# Gate_Driver_Board.net
KiCad netlist of a schematic drawn in Altium Designer
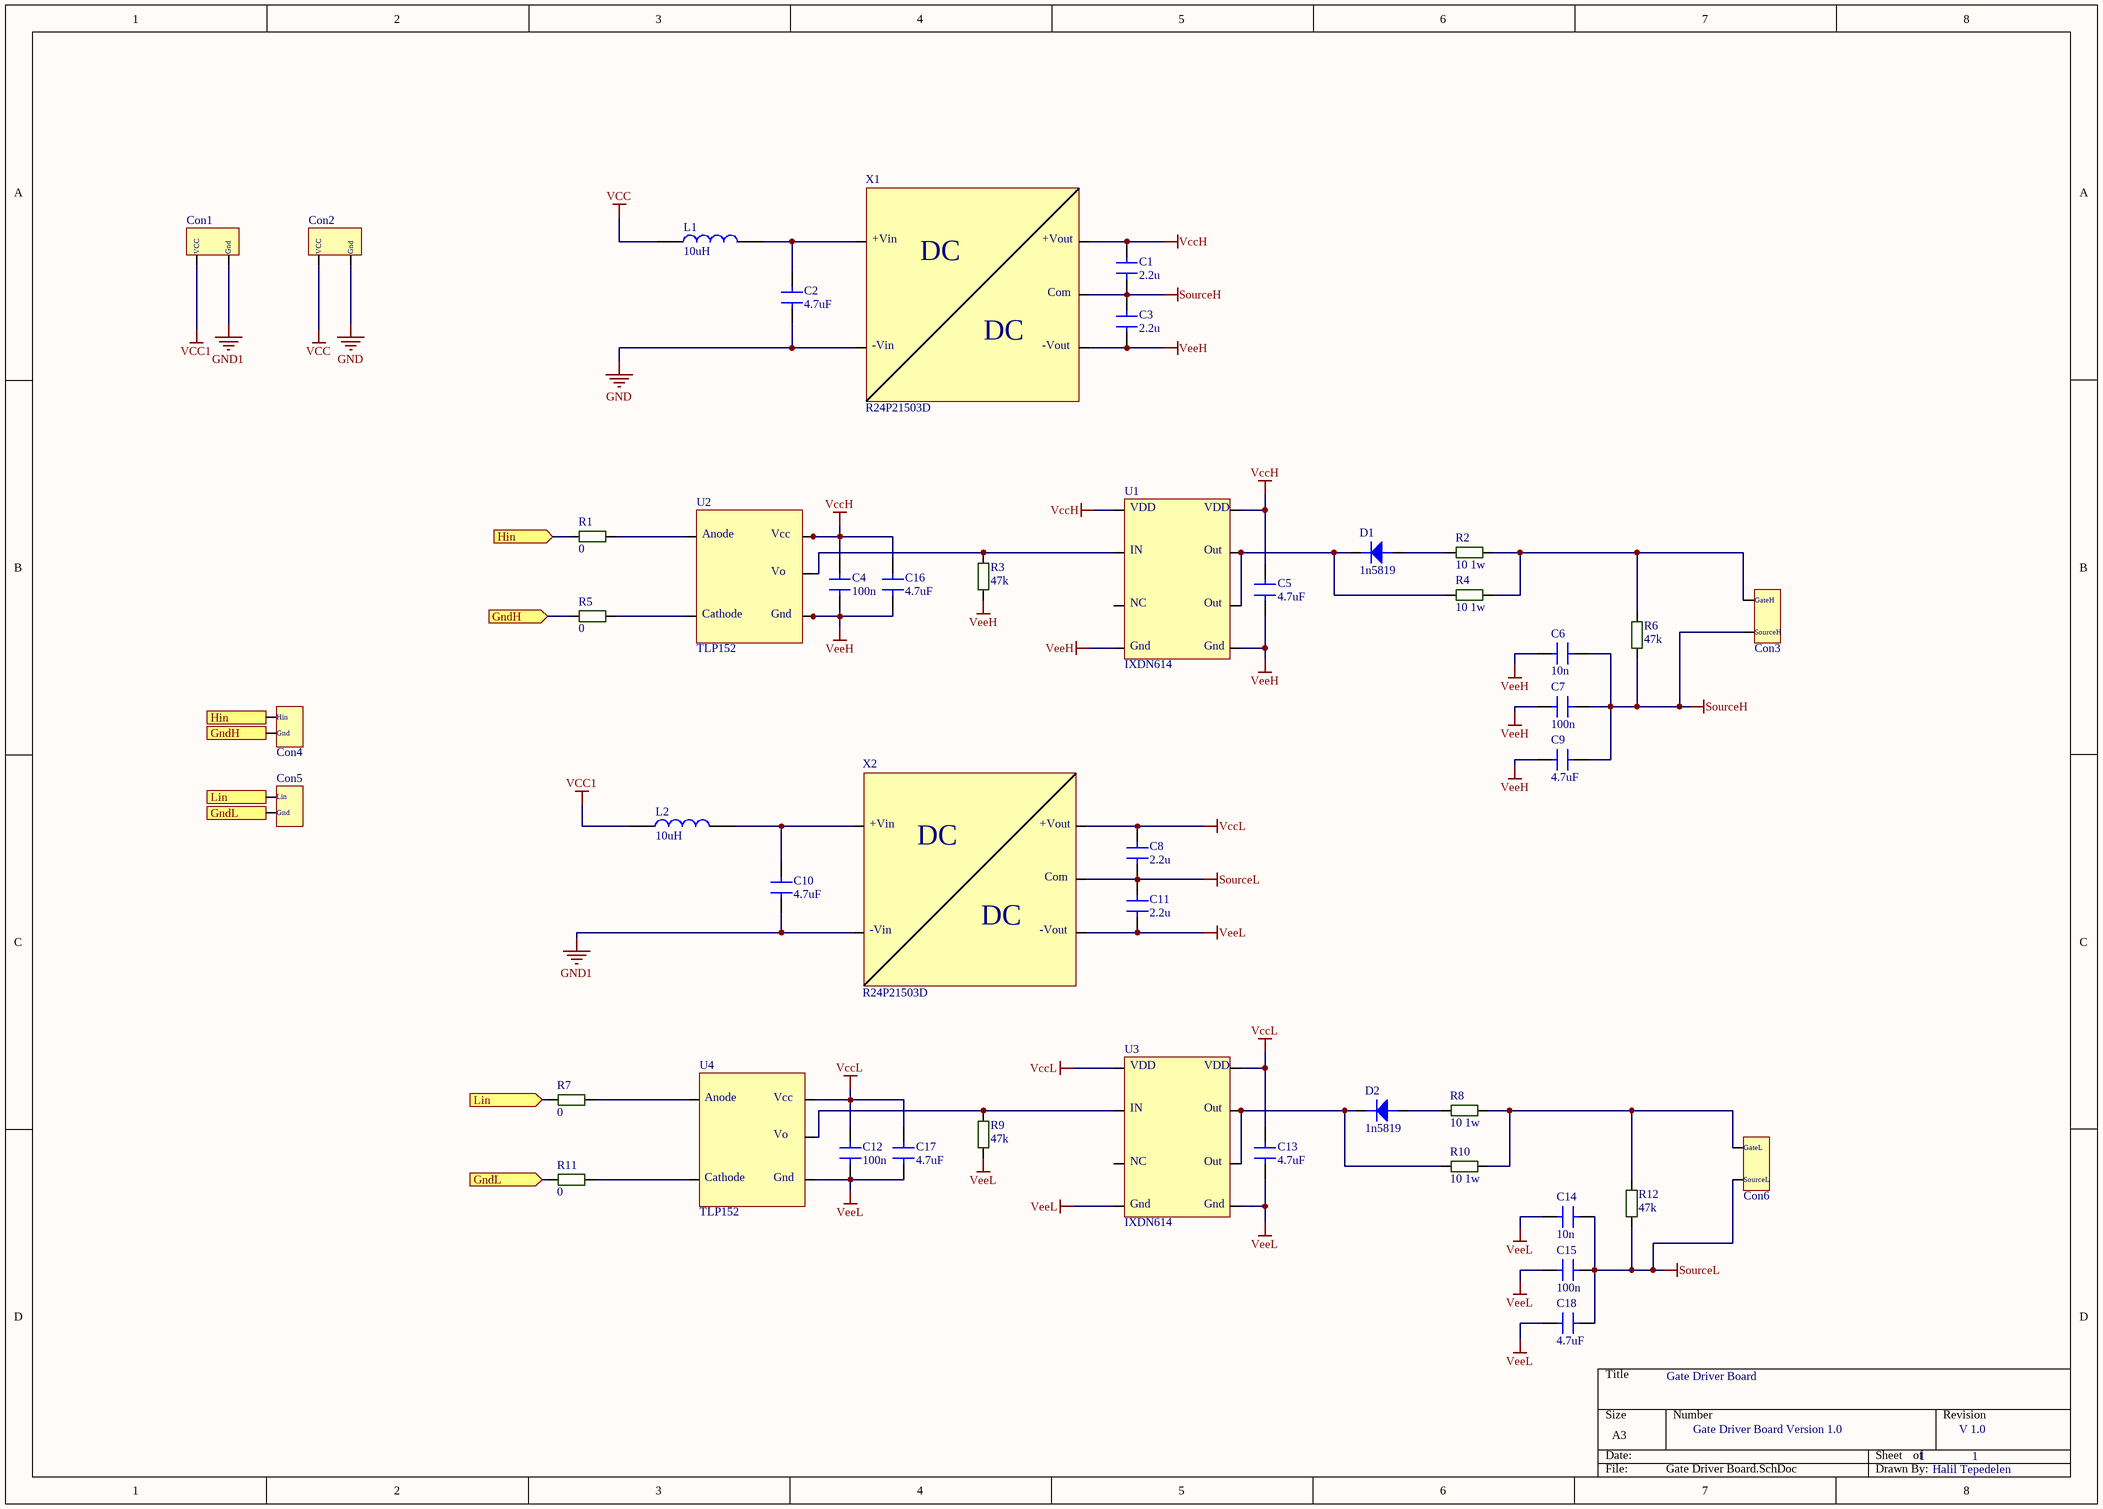
[diagram p0: Gate Driver Board.SchDoc]

(export (version "E")
  (design (tool "Eeschema 10.0.6"))
  (components
    (comp (ref "C1")
      (value "2.2u")
      (footprint "C-0805")
      (description "MLCC (2012) 0805 2.2uF 50VDC ±10% X5R")
      (fields (field (name "MANUFACTURER") "SAMSUNG") (field (name "ÖZDISAN PART NUMBER") " CL21A225KBQNNNE"))
      (libsource (lib "Gate Driver Board") (part "C-0805"))
    )
    (comp (ref "C2")
      (value "4.7uF")
      (footprint "Gate Driver Board:C-1206")
      (description "MLCC (3216) 1206 4.7uF 50VDC ±10% X7R")
      (fields (field (name "ÖZDISAN PART NUMBER") "CL31B475KBHNNNE") (field (name "MANUFACTURER") "SAMSUNG"))
      (libsource (lib "Gate Driver Board") (part "Cap1206"))
    )
    (comp (ref "C3")
      (value "2.2u")
      (footprint "C-0805")
      (description "MLCC (2012) 0805 2.2uF 50VDC ±10% X5R")
      (fields (field (name "MANUFACTURER") "SAMSUNG") (field (name "ÖZDISAN PART NUMBER") "CL21A225KBQNNNE"))
      (libsource (lib "Gate Driver Board") (part "C-0805"))
    )
    (comp (ref "C4")
      (value "100n")
      (footprint "C-0805")
      (description "MLCC (2012) 0805 100nF 50VDC ±10% X7RMLCC (2012) 0805 100nF 50VDC ±10% X7R")
      (fields (field (name "MANUFACTURER") "SAMSUNG") (field (name "ÖZDISAN PART NUMBER") "CL21B104KBCNNNC"))
      (libsource (lib "Gate Driver Board") (part "C-0805"))
    )
    (comp (ref "C5")
      (value "4.7uF")
      (footprint "Gate Driver Board:C-1206")
      (description "MLCC (3216) 1206 4.7uF 50VDC ±10% X7R")
      (fields (field (name "ÖZDISAN PART NUMBER") "CL31B475KBHNNNE") (field (name "MANUFACTURER") "SAMSUNG"))
      (libsource (lib "Gate Driver Board") (part "C-1206"))
    )
    (comp (ref "C6")
      (value "10n")
      (footprint "C-0805")
      (description "MLCC (2012) 0805 10nF 50VDC ±10% X7R")
      (fields (field (name "MANUFACTURER") "SAMSUNG") (field (name "ÖZDISAN PART NUMBER") "CL21B103KBANNNL"))
      (libsource (lib "Gate Driver Board") (part "C-0805"))
    )
    (comp (ref "C7")
      (value "100n")
      (footprint "C-0805")
      (description "MLCC (2012) 0805 100nF 50VDC ±10% X7R")
      (fields (field (name "ÖZDISAN PART NUMBER") "CL21B104KBCNNNC") (field (name "MANUFACTURER") "SAMSUNG"))
      (libsource (lib "Gate Driver Board") (part "C-0805"))
    )
    (comp (ref "C8")
      (value "2.2u")
      (footprint "C-0805")
      (description "MLCC (2012) 0805 2.2uF 50VDC ±10% X5R")
      (fields (field (name "MANUFACTURER") "SAMSUNG") (field (name "ÖZDISAN PART NUMBER") "CL21A225KBQNNNE"))
      (libsource (lib "Gate Driver Board") (part "C-0805"))
    )
    (comp (ref "C9")
      (value "4.7uF")
      (footprint "Gate Driver Board:C-1206")
      (description "MLCC (3216) 1206 4.7uF 50VDC ±10% X7R")
      (fields (field (name "ÖZDISAN PART NUMBER") " CL31B475KBHNNNE") (field (name "MANUFACTURER") "SAMSUNG"))
      (libsource (lib "Gate Driver Board") (part "Cap1206"))
    )
    (comp (ref "C10")
      (value "4.7uF")
      (footprint "Gate Driver Board:C-1206")
      (description "MLCC (3216) 1206 4.7uF 50VDC ±10% X7R")
      (fields (field (name "ÖZDISAN PART NUMBER") " CL31B475KBHNNNE") (field (name "MANUFACTURER") "SAMSUNG"))
      (libsource (lib "Gate Driver Board") (part "Cap1206"))
    )
    (comp (ref "C11")
      (value "2.2u")
      (footprint "C-0805")
      (description "MLCC (2012) 0805 2.2uF 50VDC ±10% X5R")
      (fields (field (name "MANUFACTURER") "SAMSUNG") (field (name "ÖZDISAN PART NUMBER") "CL21A225KBQNNNE"))
      (libsource (lib "Gate Driver Board") (part "C-0805"))
    )
    (comp (ref "C12")
      (value "100n")
      (footprint "C-0805")
      (description "MLCC (2012) 0805 100nF 50VDC ±10% X7R")
      (fields (field (name "ÖZDISAN PART NUMBER") "CL21B104KBCNNNC") (field (name "MANUFACTURER") "SAMSUNG"))
      (libsource (lib "Gate Driver Board") (part "C-0805"))
    )
    (comp (ref "C13")
      (value "4.7uF")
      (footprint "Gate Driver Board:C-1206")
      (description "MLCC (3216) 1206 4.7uF 50VDC ±10% X7R")
      (fields (field (name "ÖZDISAN PART NUMBER") "CL31B475KBHNNNE") (field (name "MANUFACTURER") "SAMSUNG"))
      (libsource (lib "Gate Driver Board") (part "C-1206"))
    )
    (comp (ref "C14")
      (value "10n")
      (footprint "C-0805")
      (description "MLCC (2012) 0805 10nF 50VDC ±10% X7R")
      (fields (field (name "ÖZDISAN PART NUMBER") "CL21B103KBANNNL") (field (name "MANUFACTURER") "SAMSUNG"))
      (libsource (lib "Gate Driver Board") (part "C-0805"))
    )
    (comp (ref "C15")
      (value "100n")
      (footprint "C-0805")
      (description "MLCC (2012) 0805 100nF 50VDC ±10% X7R")
      (fields (field (name "ÖZDISAN PART NUMBER") "CL21B104KBCNNNC") (field (name "MANUFACTURER") "SAMSUNG"))
      (libsource (lib "Gate Driver Board") (part "C-0805"))
    )
    (comp (ref "C16")
      (value "4.7uF")
      (footprint "Gate Driver Board:C-1206")
      (description "MLCC (3216) 1206 4.7uF 50VDC ±10% X7R")
      (fields (field (name "ÖZDISAN PART NUMBER") "CL31B475KBHNNNE") (field (name "MANUFACTURER") "SAMSUNG"))
      (libsource (lib "Gate Driver Board") (part "C-1206"))
    )
    (comp (ref "C17")
      (value "4.7uF")
      (footprint "Gate Driver Board:C-1206")
      (description "MLCC (3216) 1206 4.7uF 50VDC ±10% X7R")
      (fields (field (name "ÖZDISAN PART NUMBER") "CL31B475KBHNNNE") (field (name "MANUFACTURER") "SAMSUNG"))
      (libsource (lib "Gate Driver Board") (part "C-1206"))
    )
    (comp (ref "C18")
      (value "4.7uF")
      (footprint "Gate Driver Board:C-1206")
      (description "MLCC (3216) 1206 4.7uF 50VDC ±10% X7R")
      (fields (field (name "ÖZDISAN PART NUMBER") "CL31B475KBHNNNE") (field (name "MANUFACTURER") "SAMSUNG"))
      (libsource (lib "Gate Driver Board") (part "Cap1206"))
    )
    (comp (ref "Con1")
      (value "Connector")
      (footprint "Conn")
      (description "PIN HEADER 40PIN(1x40) 2.54mm THT V/T")
      (fields
        (field (name "ÖZDISAN PART NUMBER") "KLS1-207-1-40-S-3X9.5X15")
        (field (name "MANUFACTURER") "KLS ELECTRONIC")
      )
      (libsource (lib "Gate Driver Board") (part "Connector"))
    )
    (comp (ref "Con2")
      (value "Connector")
      (footprint "Conn")
      (description "PIN HEADER 40PIN(1x40) 2.54mm THT V/T")
      (fields
        (field (name "ÖZDISAN PART NUMBER") "KLS1-207-1-40-S-3X9.5X15")
        (field (name "MANUFACTURER") "KLS ELECTRONIC")
      )
      (libsource (lib "Gate Driver Board") (part "Connector"))
    )
    (comp (ref "Con3")
      (value "Connector2_1")
      (footprint "Conn")
      (description "PIN HEADER 40PIN(1x40) 2.54mm THT V/T")
      (fields
        (field (name "ÖZDISAN PART NUMBER") " KLS1-207-1-40-S-3X9.5X15")
        (field (name "MANUFACTURER") "KLS ELECTRONIC")
      )
      (libsource (lib "Gate Driver Board") (part "Connector2_1"))
    )
    (comp (ref "Con4")
      (value "Connector2")
      (footprint "Conn")
      (description "PIN HEADER 40PIN(1x40) 2.54mm THT V/T")
      (fields
        (field (name "ÖZDISAN PART NUMBER") "KLS1-207-1-40-S-3X9.5X15")
        (field (name "MANUFACTURER") "KLS ELECTRONIC")
      )
      (libsource (lib "Gate Driver Board") (part "Connector2"))
    )
    (comp (ref "Con5")
      (value "Connector3")
      (footprint "Conn")
      (description "PIN HEADER 40PIN(1x40) 2.54mm THT V/T")
      (fields
        (field (name "ÖZDISAN PART NUMBER") "KLS1-207-1-40-S-3X9.5X15")
        (field (name "MANUFACTURER") "KLS ELECTRONIC")
      )
      (libsource (lib "Gate Driver Board") (part "Connector3"))
    )
    (comp (ref "Con6")
      (value "Connector2_2")
      (footprint "Conn")
      (description "PIN HEADER 40PIN(1x40) 2.54mm THT V/T")
      (fields
        (field (name "ÖZDISAN PART NUMBER") "KLS1-207-1-40-S-3X9.5X15")
        (field (name "MANUFACTURER") "KLS ELECTRONIC")
      )
      (libsource (lib "Gate Driver Board") (part "Connector2_2"))
    )
    (comp (ref "D1")
      (value "1n5819")
      (footprint "LFI Power Board PcbLib1:SOD123")
      (description "DIODE SCHOTTKY 1A 40V SOD123")
      (fields (field (name "MANUFACTURER") "HOTTECH") (field (name "ÖZDISAN PART NUMBER") "B5819W"))
      (libsource (lib "Gate Driver Board") (part "1N4148W-E3-18"))
    )
    (comp (ref "D2")
      (value "1n5819")
      (footprint "LFI Power Board PcbLib1:SOD123")
      (description "Diode Small Signal Switching 100V 0.15A 2-Pin SOD-123 T/R")
      (fields (field (name "ÖZDISAN PART NUMBER") "B5819W") (field (name "MANUFACTURER") "HOTTECH"))
      (libsource (lib "Gate Driver Board") (part "1N4148W-E3-18"))
    )
    (comp (ref "L1")
      (value "10uH")
      (footprint "Gate Driver Board:WE-TPC_282892")
      (description "INDUCTOR POWER 10UH 2.8X2.8X2.8MM SMD")
      (fields (field (name "ÖZDISAN PART NUMBER") "744025100") (field (name "MANUFACTURER") "WURTH"))
      (libsource (lib "Gate Driver Board") (part "inductor"))
    )
    (comp (ref "L2")
      (value "10uH")
      (footprint "WE-TPC_282892")
      (description "INDUCTOR POWER 10UH 2.8X2.8X2.8MM SMD")
      (fields (field (name "ÖZDISAN PART NUMBER") "744025100") (field (name "MANUFACTURER") "WURTH"))
      (libsource (lib "Gate Driver Board") (part "inductor"))
    )
    (comp (ref "R1")
      (value "0")
      (footprint "Gate Driver Board:R-0805")
      (description "RES.(2012) 0805 0 Ohms 5% 1/8W-S 800PPM")
      (fields (field (name "MANUFACTURER") "ROYALOHM") (field (name "ÖZDISAN PART NUMBER") "0805S8J0000T5E"))
      (libsource (lib "Gate Driver Board") (part "Res0805"))
    )
    (comp (ref "R2")
      (value "10 1w")
      (footprint "R-2512")
      (description "RES.(6432) 2512 5.1 Ohms 5% 1W 400PPM")
      (fields (field (name "MANUFACTURER") "ROYALOHM") (field (name "ÖZDISAN PART NUMBER") "25121WJ051JT4E"))
      (libsource (lib "Gate Driver Board") (part "R-2512"))
    )
    (comp (ref "R3")
      (value "47k")
      (footprint "Gate Driver Board:R-0805")
      (description "RES.(2012) 0805 47K Ohms 5% 1/8W-S 100PPM")
      (fields (field (name "MANUFACTURER") "ROYALOHM") (field (name "ÖZDISAN PART NUMBER") "0805S8J0473T5E"))
      (libsource (lib "Gate Driver Board") (part "Res0805"))
    )
    (comp (ref "R4")
      (value "10 1w")
      (footprint "R-2512")
      (description "RES.(6432) 2512 5.1 Ohms 5% 1W 400PPM")
      (fields (field (name "ÖZDISAN PART NUMBER") "25121WJ051JT4E") (field (name "MANUFACTURER") "ROYALOHM"))
      (libsource (lib "Gate Driver Board") (part "R-2512"))
    )
    (comp (ref "R5")
      (value "0")
      (footprint "Gate Driver Board:R-0805")
      (description "RES.(2012) 0805 0 Ohms 5% 1/8W-S 800PPM")
      (fields (field (name "MANUFACTURER") "ROYALOHM") (field (name "ÖZDISAN PART NUMBER") "0805S8J0000T5E"))
      (libsource (lib "Gate Driver Board") (part "Res0805"))
    )
    (comp (ref "R6")
      (value "47k")
      (footprint "Gate Driver Board:R-0805")
      (description "RES.(2012) 0805 47K Ohms 5% 1/8W-S 100PPM")
      (fields (field (name "ÖZDISAN PART NUMBER") "0805S8J0473T5E") (field (name "MANUFACTURER") "ROYALOHM"))
      (libsource (lib "Gate Driver Board") (part "Res0805"))
    )
    (comp (ref "R7")
      (value "0")
      (footprint "Gate Driver Board:R-0805")
      (description "RES.(2012) 0805 0 Ohms 5% 1/8W-S 800PPM")
      (fields (field (name "ÖZDISAN PART NUMBER") "0805S8J0000T5E") (field (name "MANUFACTURER") "ROYALOHM"))
      (libsource (lib "Gate Driver Board") (part "Res0805"))
    )
    (comp (ref "R8")
      (value "10 1w")
      (footprint "R-2512")
      (description "RES.(6432) 2512 5.1 Ohms 5% 1W 400PPM")
      (fields (field (name "ÖZDISAN PART NUMBER") "25121WJ051JT4E") (field (name "MANUFACTURER") "ROYALOHM"))
      (libsource (lib "Gate Driver Board") (part "R-2512"))
    )
    (comp (ref "R9")
      (value "47k")
      (footprint "Gate Driver Board:R-0805")
      (description "RES.(2012) 0805 47K Ohms 5% 1/8W-S 100PPM")
      (fields (field (name "ÖZDISAN PART NUMBER") "0805S8J0473T5E") (field (name "MANUFACTURER") "ROYALOHM"))
      (libsource (lib "Gate Driver Board") (part "Res0805"))
    )
    (comp (ref "R10")
      (value "10 1w")
      (footprint "R-2512")
      (description "RES.(6432) 2512 5.1 Ohms 5% 1W 400PPM")
      (fields (field (name "MANUFACTURER") "ROYALOHM") (field (name "ÖZDISAN PART NUMBER") "25121WJ051JT4E"))
      (libsource (lib "Gate Driver Board") (part "R-2512"))
    )
    (comp (ref "R11")
      (value "0")
      (footprint "Gate Driver Board:R-0805")
      (description "RES.(2012) 0805 0 Ohms 5% 1/8W-S 800PPM")
      (fields (field (name "MANUFACTURER") "ROYALOHM") (field (name "ÖZDISAN PART NUMBER") "0805S8J0000T5E"))
      (libsource (lib "Gate Driver Board") (part "Res0805"))
    )
    (comp (ref "R12")
      (value "47k")
      (footprint "Gate Driver Board:R-0805")
      (description "RES.(2012) 0805 47K Ohms 5% 1/8W-S 100PPM")
      (fields (field (name "ÖZDISAN PART NUMBER") "0805S8J0473T5E") (field (name "MANUFACTURER") "ROYALOHM"))
      (libsource (lib "Gate Driver Board") (part "Res0805"))
    )
    (comp (ref "U1")
      (value "IXDN614")
      (footprint "FAN3122 Soic8")
      (description "IC-614 DRIVER MOSFET/IGBT SOIC8 IXYS CLARE")
      (fields (field (name "MANUFACTURER") "IXYS CLARE") (field (name "ÖZDISAN PART NUMBER") "IXDN614SI"))
      (libsource (lib "Gate Driver Board") (part "IXDN614SITR"))
    )
    (comp (ref "U2")
      (value "TLP152")
      (footprint "TLP152")
      (description "IC-152 PHOTOCOUPLER GATE DRIVE SO6 TOSHIBA")
      (fields (field (name "ÖZDISAN PART NUMBER") "TLP152(TPL,E") (field (name "MANUFACTURER") "TOSHIBA"))
      (libsource (lib "Gate Driver Board") (part "TLP152(TPL,E"))
    )
    (comp (ref "U3")
      (value "IXDN614")
      (footprint "FAN3122 Soic8")
      (description "IC-614 DRIVER MOSFET/IGBT SOIC8 IXYS CLARE")
      (fields (field (name "MANUFACTURER") "IXYS CLARE") (field (name "ÖZDISAN PART NUMBER") "IXDN614SI"))
      (libsource (lib "Gate Driver Board") (part "IXDN614SITR"))
    )
    (comp (ref "U4")
      (value "TLP152")
      (footprint "TLP152")
      (description "IC-152 PHOTOCOUPLER GATE DRIVE SO6 TOSHIBA")
      (fields (field (name "ÖZDISAN PART NUMBER") "TLP152(TPL,E") (field (name "MANUFACTURER") "TOSHIBA"))
      (libsource (lib "Gate Driver Board") (part "TLP152(TPL,E"))
    )
    (comp (ref "X1")
      (value "R24P21503D")
      (footprint "SIP7")
      (description "DC/DC CONV 2W 12VDC +15/-3VDC 93mA/-185mA SIP7")
      (fields (field (name "MANUFACTURER") "RECOM") (field (name "ÖZDISAN PART NUMBER") "R12P21503D"))
      (libsource (lib "Gate Driver Board") (part "R24P21503D"))
    )
    (comp (ref "X2")
      (value "R24P21503D")
      (footprint "SIP7")
      (description "DC/DC CONV 2W 12VDC +15/-3VDC 93mA/-185mA SIP7")
      (fields (field (name "MANUFACTURER") "RECOM") (field (name "ÖZDISAN PART NUMBER") "R12P21503D"))
      (libsource (lib "Gate Driver Board") (part "R24P21503D"))
    )
  )
  (nets
    (net (code "1") (name "/GndH") (class "Default")
      (node (ref "Con4") (pin "2") (pinfunction "2_2") (pintype "passive"))
      (node (ref "R5") (pin "1") (pinfunction "1_1") (pintype "passive"))
    )
    (net (code "2") (name "/GndL") (class "Default")
      (node (ref "Con5") (pin "2") (pinfunction "2_2") (pintype "passive"))
      (node (ref "R11") (pin "1") (pinfunction "1_1") (pintype "passive"))
    )
    (net (code "3") (name "/Hin") (class "Default")
      (node (ref "Con4") (pin "1") (pinfunction "1_1") (pintype "passive"))
      (node (ref "R1") (pin "1") (pinfunction "1_1") (pintype "passive"))
    )
    (net (code "4") (name "/Lin") (class "Default")
      (node (ref "Con5") (pin "1") (pinfunction "1_1") (pintype "passive"))
      (node (ref "R7") (pin "1") (pinfunction "1_1") (pintype "passive"))
    )
    (net (code "5") (name "GND") (class "Default")
      (node (ref "C2") (pin "1") (pinfunction "1_1") (pintype "passive"))
      (node (ref "Con2") (pin "2") (pinfunction "2_2") (pintype "passive"))
      (node (ref "X1") (pin "2") (pinfunction "2_2") (pintype "passive"))
    )
    (net (code "6") (name "GND1") (class "Default")
      (node (ref "C10") (pin "1") (pinfunction "1_1") (pintype "passive"))
      (node (ref "Con1") (pin "2") (pinfunction "2_2") (pintype "passive"))
      (node (ref "X2") (pin "2") (pinfunction "2_2") (pintype "passive"))
    )
    (net (code "7") (name "Net-(C2-Pad2)") (class "Default")
      (node (ref "C2") (pin "2") (pinfunction "2_2") (pintype "passive"))
      (node (ref "L1") (pin "2") (pinfunction "2_2") (pintype "passive"))
      (node (ref "X1") (pin "1") (pinfunction "1_1") (pintype "passive"))
    )
    (net (code "8") (name "Net-(C10-Pad2)") (class "Default")
      (node (ref "C10") (pin "2") (pinfunction "2_2") (pintype "passive"))
      (node (ref "L2") (pin "2") (pinfunction "2_2") (pintype "passive"))
      (node (ref "X2") (pin "1") (pinfunction "1_1") (pintype "passive"))
    )
    (net (code "9") (name "Net-(Con3-Pad1)") (class "Default")
      (node (ref "Con3") (pin "1") (pinfunction "1_1") (pintype "passive"))
      (node (ref "R2") (pin "2") (pinfunction "2_2") (pintype "passive"))
      (node (ref "R4") (pin "2") (pinfunction "2_2") (pintype "passive"))
      (node (ref "R6") (pin "2") (pinfunction "2_2") (pintype "passive"))
    )
    (net (code "10") (name "Net-(Con6-Pad1)") (class "Default")
      (node (ref "Con6") (pin "1") (pinfunction "1_1") (pintype "passive"))
      (node (ref "R10") (pin "2") (pinfunction "2_2") (pintype "passive"))
      (node (ref "R12") (pin "2") (pinfunction "2_2") (pintype "passive"))
      (node (ref "R8") (pin "2") (pinfunction "2_2") (pintype "passive"))
    )
    (net (code "11") (name "Net-(D1-Pada)") (class "Default")
      (node (ref "D1") (pin "a") (pinfunction "a_a") (pintype "passive"))
      (node (ref "R2") (pin "1") (pinfunction "1_1") (pintype "passive"))
    )
    (net (code "12") (name "Net-(D1-Padk)") (class "Default")
      (node (ref "D1") (pin "k") (pinfunction "k_k") (pintype "passive"))
      (node (ref "R4") (pin "1") (pinfunction "1_1") (pintype "passive"))
      (node (ref "U1") (pin "6") (pinfunction "6_6") (pintype "passive"))
      (node (ref "U1") (pin "7") (pinfunction "7_7") (pintype "passive"))
    )
    (net (code "13") (name "Net-(D2-Pada)") (class "Default")
      (node (ref "D2") (pin "a") (pinfunction "a_a") (pintype "passive"))
      (node (ref "R8") (pin "1") (pinfunction "1_1") (pintype "passive"))
    )
    (net (code "14") (name "Net-(D2-Padk)") (class "Default")
      (node (ref "D2") (pin "k") (pinfunction "k_k") (pintype "passive"))
      (node (ref "R10") (pin "1") (pinfunction "1_1") (pintype "passive"))
      (node (ref "U3") (pin "6") (pinfunction "6_6") (pintype "passive"))
      (node (ref "U3") (pin "7") (pinfunction "7_7") (pintype "passive"))
    )
    (net (code "15") (name "Net-(R1-Pad2)") (class "Default")
      (node (ref "R1") (pin "2") (pinfunction "2_2") (pintype "passive"))
      (node (ref "U2") (pin "1") (pinfunction "1_1") (pintype "passive"))
    )
    (net (code "16") (name "Net-(R3-Pad2)") (class "Default")
      (node (ref "R3") (pin "2") (pinfunction "2_2") (pintype "passive"))
      (node (ref "U1") (pin "2") (pinfunction "2_2") (pintype "passive"))
      (node (ref "U2") (pin "4") (pinfunction "4_4") (pintype "passive"))
    )
    (net (code "17") (name "Net-(R5-Pad2)") (class "Default")
      (node (ref "R5") (pin "2") (pinfunction "2_2") (pintype "passive"))
      (node (ref "U2") (pin "2") (pinfunction "2_2") (pintype "passive"))
    )
    (net (code "18") (name "Net-(R7-Pad2)") (class "Default")
      (node (ref "R7") (pin "2") (pinfunction "2_2") (pintype "passive"))
      (node (ref "U4") (pin "1") (pinfunction "1_1") (pintype "passive"))
    )
    (net (code "19") (name "Net-(R9-Pad2)") (class "Default")
      (node (ref "R9") (pin "2") (pinfunction "2_2") (pintype "passive"))
      (node (ref "U3") (pin "2") (pinfunction "2_2") (pintype "passive"))
      (node (ref "U4") (pin "4") (pinfunction "4_4") (pintype "passive"))
    )
    (net (code "20") (name "Net-(R11-Pad2)") (class "Default")
      (node (ref "R11") (pin "2") (pinfunction "2_2") (pintype "passive"))
      (node (ref "U4") (pin "2") (pinfunction "2_2") (pintype "passive"))
    )
    (net (code "21") (name "SourceH") (class "Default")
      (node (ref "C1") (pin "1") (pinfunction "1_1") (pintype "passive"))
      (node (ref "C3") (pin "2") (pinfunction "2_2") (pintype "passive"))
      (node (ref "C6") (pin "1") (pinfunction "1_1") (pintype "passive"))
      (node (ref "C7") (pin "1") (pinfunction "1_1") (pintype "passive"))
      (node (ref "C9") (pin "2") (pinfunction "2_2") (pintype "passive"))
      (node (ref "Con3") (pin "2") (pinfunction "2_2") (pintype "passive"))
      (node (ref "R6") (pin "1") (pinfunction "1_1") (pintype "passive"))
      (node (ref "X1") (pin "6") (pinfunction "6_6") (pintype "passive"))
    )
    (net (code "22") (name "SourceL") (class "Default")
      (node (ref "C11") (pin "2") (pinfunction "2_2") (pintype "passive"))
      (node (ref "C14") (pin "1") (pinfunction "1_1") (pintype "passive"))
      (node (ref "C15") (pin "1") (pinfunction "1_1") (pintype "passive"))
      (node (ref "C18") (pin "2") (pinfunction "2_2") (pintype "passive"))
      (node (ref "C8") (pin "1") (pinfunction "1_1") (pintype "passive"))
      (node (ref "Con6") (pin "2") (pinfunction "2_2") (pintype "passive"))
      (node (ref "R12") (pin "1") (pinfunction "1_1") (pintype "passive"))
      (node (ref "X2") (pin "6") (pinfunction "6_6") (pintype "passive"))
    )
    (net (code "23") (name "VCC") (class "Default")
      (node (ref "Con2") (pin "1") (pinfunction "1_1") (pintype "passive"))
      (node (ref "L1") (pin "1") (pinfunction "1_1") (pintype "passive"))
    )
    (net (code "24") (name "VCC1") (class "Default")
      (node (ref "Con1") (pin "1") (pinfunction "1_1") (pintype "passive"))
      (node (ref "L2") (pin "1") (pinfunction "1_1") (pintype "passive"))
    )
    (net (code "25") (name "VccH") (class "Default")
      (node (ref "C1") (pin "2") (pinfunction "2_2") (pintype "passive"))
      (node (ref "C16") (pin "2") (pinfunction "2_2") (pintype "passive"))
      (node (ref "C4") (pin "2") (pinfunction "2_2") (pintype "passive"))
      (node (ref "C5") (pin "2") (pinfunction "2_2") (pintype "passive"))
      (node (ref "U1") (pin "1") (pinfunction "1_1") (pintype "passive"))
      (node (ref "U1") (pin "8") (pinfunction "8_8") (pintype "passive"))
      (node (ref "U2") (pin "5") (pinfunction "5_5") (pintype "passive"))
      (node (ref "X1") (pin "7") (pinfunction "7_7") (pintype "passive"))
    )
    (net (code "26") (name "VccL") (class "Default")
      (node (ref "C12") (pin "2") (pinfunction "2_2") (pintype "passive"))
      (node (ref "C13") (pin "2") (pinfunction "2_2") (pintype "passive"))
      (node (ref "C17") (pin "2") (pinfunction "2_2") (pintype "passive"))
      (node (ref "C8") (pin "2") (pinfunction "2_2") (pintype "passive"))
      (node (ref "U3") (pin "1") (pinfunction "1_1") (pintype "passive"))
      (node (ref "U3") (pin "8") (pinfunction "8_8") (pintype "passive"))
      (node (ref "U4") (pin "5") (pinfunction "5_5") (pintype "passive"))
      (node (ref "X2") (pin "7") (pinfunction "7_7") (pintype "passive"))
    )
    (net (code "27") (name "VeeH") (class "Default")
      (node (ref "C16") (pin "1") (pinfunction "1_1") (pintype "passive"))
      (node (ref "C3") (pin "1") (pinfunction "1_1") (pintype "passive"))
      (node (ref "C4") (pin "1") (pinfunction "1_1") (pintype "passive"))
      (node (ref "C5") (pin "1") (pinfunction "1_1") (pintype "passive"))
      (node (ref "C6") (pin "2") (pinfunction "2_2") (pintype "passive"))
      (node (ref "C7") (pin "2") (pinfunction "2_2") (pintype "passive"))
      (node (ref "C9") (pin "1") (pinfunction "1_1") (pintype "passive"))
      (node (ref "R3") (pin "1") (pinfunction "1_1") (pintype "passive"))
      (node (ref "U1") (pin "4") (pinfunction "4_4") (pintype "passive"))
      (node (ref "U1") (pin "5") (pinfunction "5_5") (pintype "passive"))
      (node (ref "U2") (pin "3") (pinfunction "3_3") (pintype "passive"))
      (node (ref "X1") (pin "5") (pinfunction "5_5") (pintype "passive"))
    )
    (net (code "28") (name "VeeL") (class "Default")
      (node (ref "C11") (pin "1") (pinfunction "1_1") (pintype "passive"))
      (node (ref "C12") (pin "1") (pinfunction "1_1") (pintype "passive"))
      (node (ref "C13") (pin "1") (pinfunction "1_1") (pintype "passive"))
      (node (ref "C14") (pin "2") (pinfunction "2_2") (pintype "passive"))
      (node (ref "C15") (pin "2") (pinfunction "2_2") (pintype "passive"))
      (node (ref "C17") (pin "1") (pinfunction "1_1") (pintype "passive"))
      (node (ref "C18") (pin "1") (pinfunction "1_1") (pintype "passive"))
      (node (ref "R9") (pin "1") (pinfunction "1_1") (pintype "passive"))
      (node (ref "U3") (pin "4") (pinfunction "4_4") (pintype "passive"))
      (node (ref "U3") (pin "5") (pinfunction "5_5") (pintype "passive"))
      (node (ref "U4") (pin "3") (pinfunction "3_3") (pintype "passive"))
      (node (ref "X2") (pin "5") (pinfunction "5_5") (pintype "passive"))
    )
    (net (code "29") (name "unconnected-(U1-Pad3)") (class "Default")
      (node (ref "U1") (pin "3") (pinfunction "3_3") (pintype "passive"))
    )
    (net (code "30") (name "unconnected-(U3-Pad3)") (class "Default")
      (node (ref "U3") (pin "3") (pinfunction "3_3") (pintype "passive"))
    )
  )
)
